# MAX931.net
KiCad netlist of a schematic drawn in Altium Designer
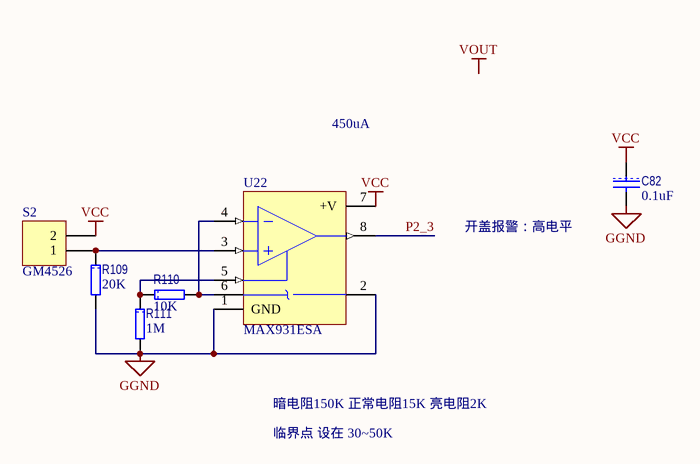
[diagram p0: 开盒检测_MAX931.SchDoc]

(export (version "E")
  (design (tool "Eeschema 10.0.6"))
  (components
    (comp (ref "C82")
      (value "0.1uF")
      (footprint "1608[0603]C")
      (description "多层陶瓷电容器MLCC - SMD/SMT 0603 0.1uF 50volts X7R 10%")
      (fields (field (name "MANUFACTURER") "TDK") (field (name "MANUFACTURER PART NUMBER") "C1608X7R1H104K"))
      (libsource (lib "*") (part "CAP"))
    )
    (comp (ref "R109")
      (value "20K")
      (footprint "1608[0603]R")
      (description "厚膜电阻器 - SMD 1/10watt 15Kohms 1%")
      (fields (field (name "Comment") "CRCW060315K0FKEA"))
      (libsource (lib "10K 1%") (part "RES"))
    )
    (comp (ref "R110")
      (value "10K")
      (footprint "1608[0603]R")
      (description "厚膜电阻器 - SMD 1/10watt 10Kohms 1%")
      (fields
        (field (name "MANUFACTURER") "Vishay / Dale")
        (field (name "MANUFACTURER PART NUMBER") "CRCW060310K0FKEA")
      )
      (libsource (lib "10K 1%") (part "RES"))
    )
    (comp (ref "R111")
      (value "1M")
      (footprint "1608[0603]R")
      (description "厚膜电阻器 - SMD 1/10watt 10Kohms 1%")
      (fields
        (field (name "MANUFACTURER") "Vishay / Dale")
        (field (name "MANUFACTURER PART NUMBER") "CRCW060310K0FKEA")
      )
      (libsource (lib "10K 1%") (part "RES"))
    )
    (comp (ref "S2")
      (value "GM4526")
      (footprint "GM4526")
      (description "插针 光敏传感器")
      (fields (field (name "PUBLISHER") "Altium Limited"))
      (libsource (lib "Miscellaneous Connectors") (part "Header 2"))
    )
    (comp (ref "U22")
      (value "MAX931ESA")
      (footprint "NSO8_N")
      (description "Ultra Low-Power, Low-Cost Comparator with 2% Reference")
      (fields (field (name "PUBLISHER") "Altium Limited"))
      (libsource (lib "Maxim Analog Comparator") (part "MAX931ESA"))
    )
  )
  (nets
    (net (code "1") (name "/P2_3") (class "Default")
      (node (ref "U22") (pin "8") (pinfunction "OUT_8") (pintype "output"))
    )
    (net (code "2") (name "GGND") (class "Default")
      (node (ref "C82") (pin "2") (pinfunction "2_2") (pintype "passive"))
      (node (ref "R109") (pin "2") (pinfunction "2_2") (pintype "passive"))
      (node (ref "R111") (pin "2") (pinfunction "2_2") (pintype "passive"))
      (node (ref "U22") (pin "1") (pinfunction "GND_1") (pintype "power_in"))
      (node (ref "U22") (pin "2") (pinfunction "-V_2") (pintype "power_in"))
    )
    (net (code "3") (name "Net-(U22-HYST)") (class "Default")
      (node (ref "R110") (pin "1") (pinfunction "1_1") (pintype "passive"))
      (node (ref "R111") (pin "1") (pinfunction "1_1") (pintype "passive"))
      (node (ref "U22") (pin "5") (pinfunction "HYST_5") (pintype "input"))
    )
    (net (code "4") (name "Net-(U22-IN+)") (class "Default")
      (node (ref "R109") (pin "1") (pinfunction "1_1") (pintype "passive"))
      (node (ref "S2") (pin "1") (pinfunction "1_1") (pintype "passive"))
      (node (ref "U22") (pin "3") (pinfunction "IN+_3") (pintype "input"))
    )
    (net (code "5") (name "Net-(U22-IN-)") (class "Default")
      (node (ref "R110") (pin "2") (pinfunction "2_2") (pintype "passive"))
      (node (ref "U22") (pin "4") (pinfunction "IN-_4") (pintype "input"))
      (node (ref "U22") (pin "6") (pinfunction "REF_6") (pintype "passive"))
    )
    (net (code "6") (name "VCC") (class "Default")
      (node (ref "C82") (pin "1") (pinfunction "1_1") (pintype "passive"))
      (node (ref "S2") (pin "2") (pinfunction "2_2") (pintype "passive"))
      (node (ref "U22") (pin "7") (pinfunction "+V_7") (pintype "power_in"))
    )
  )
)
